# doorbell-controller.net
KiCad netlist of a schematic drawn in EAGLE
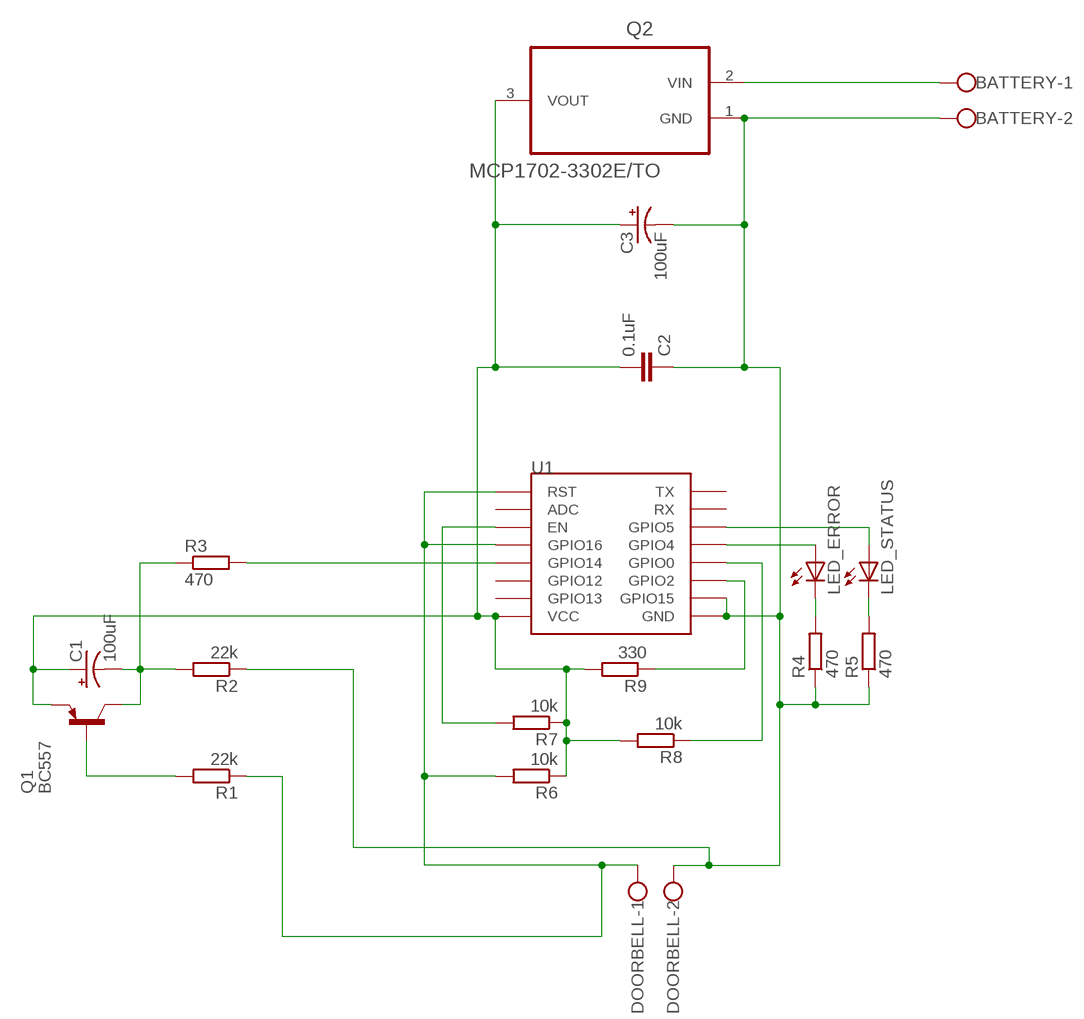
[diagram p0: schematic, sheet 1]

(export (version "E")
  (design (tool "Eeschema 10.0.6"))
  (components
    (comp (ref "BATTERY")
      (value "W237-102")
      (footprint "eagle-import:W237-102")
      (fields (field (name "MPN") "237-102"))
      (libsource (lib "eagle-import") (part "W237-102"))
    )
    (comp (ref "C1")
      (value "100uF")
      (footprint "eagle-import:E2,5-6E")
      (libsource (lib "eagle-import") (part "CPOL-USE2,5-6E"))
    )
    (comp (ref "C2")
      (value "0.1uF")
      (footprint "eagle-import:C025-025X050")
      (libsource (lib "eagle-import") (part "C-EU025-025X050"))
    )
    (comp (ref "C3")
      (value "100uF")
      (footprint "eagle-import:E2,5-6E")
      (libsource (lib "eagle-import") (part "CPOL-USE2,5-6E"))
    )
    (comp (ref "DOORBELL")
      (value "W237-102")
      (footprint "eagle-import:W237-102")
      (fields (field (name "MPN") "237-102"))
      (libsource (lib "eagle-import") (part "W237-102"))
    )
    (comp (ref "LED_ERROR")
      (value "LED5MM")
      (footprint "eagle-import:LED5MM")
      (libsource (lib "eagle-import") (part "LED5MM"))
    )
    (comp (ref "LED_STATUS")
      (value "LED5MM")
      (footprint "eagle-import:LED5MM")
      (libsource (lib "eagle-import") (part "LED5MM"))
    )
    (comp (ref "Q1")
      (value "BC557")
      (footprint "eagle-import:TO92")
      (libsource (lib "eagle-import") (part "BC557"))
    )
    (comp (ref "Q2")
      (value "MCP1702-3302E/TO")
      (footprint "eagle-import:TO127P254X533-3")
      (libsource (lib "eagle-import") (part "MCP1702-3302E/TO"))
    )
    (comp (ref "R1")
      (value "22k")
      (footprint "eagle-import:0204_7")
      (libsource (lib "eagle-import") (part "R-EU_0204/7"))
    )
    (comp (ref "R2")
      (value "22k")
      (footprint "eagle-import:0204_7")
      (libsource (lib "eagle-import") (part "R-EU_0204/7"))
    )
    (comp (ref "R3")
      (value "470")
      (footprint "eagle-import:0204_7")
      (libsource (lib "eagle-import") (part "R-EU_0204/7"))
    )
    (comp (ref "R4")
      (value "470")
      (footprint "eagle-import:0204_7")
      (libsource (lib "eagle-import") (part "R-EU_0204/7"))
    )
    (comp (ref "R5")
      (value "470")
      (footprint "eagle-import:0204_7")
      (libsource (lib "eagle-import") (part "R-EU_0204/7"))
    )
    (comp (ref "R6")
      (value "10k")
      (footprint "eagle-import:0204_7")
      (libsource (lib "eagle-import") (part "R-EU_0204/7"))
    )
    (comp (ref "R7")
      (value "10k")
      (footprint "eagle-import:0204_7")
      (libsource (lib "eagle-import") (part "R-EU_0204/7"))
    )
    (comp (ref "R8")
      (value "10k")
      (footprint "eagle-import:0204_7")
      (libsource (lib "eagle-import") (part "R-EU_0204/7"))
    )
    (comp (ref "R9")
      (value "330")
      (footprint "eagle-import:0204_7")
      (libsource (lib "eagle-import") (part "R-EU_0204/7"))
    )
    (comp (ref "U1")
      (value "ESP12-TR")
      (footprint "eagle-import:ESP12-TR")
      (libsource (lib "eagle-import") (part "ESP12-TR"))
    )
  )
  (nets
    (net (code "1") (name "Net-(BATTERYA-KL)") (class "Default")
      (node (ref "BATTERY") (pin "1") (pinfunction "KL_1") (pintype "passive"))
      (node (ref "Q2") (pin "2") (pinfunction "VIN_2") (pintype "input"))
    )
    (net (code "2") (name "Net-(BATTERYB-KL)") (class "Default")
      (node (ref "BATTERY") (pin "2") (pinfunction "KL_2") (pintype "passive"))
      (node (ref "C2") (pin "1") (pinfunction "1_1") (pintype "passive"))
      (node (ref "C3") (pin "-") (pinfunction "-_-") (pintype "passive"))
      (node (ref "DOORBELL") (pin "2") (pinfunction "KL_2") (pintype "passive"))
      (node (ref "Q2") (pin "1") (pinfunction "GND_1") (pintype "passive"))
      (node (ref "R2") (pin "1") (pinfunction "1_1") (pintype "passive"))
      (node (ref "R4") (pin "1") (pinfunction "1_1") (pintype "passive"))
      (node (ref "R5") (pin "1") (pinfunction "1_1") (pintype "passive"))
      (node (ref "U1") (pin "GND") (pinfunction "GND_GND") (pintype "bidirectional"))
      (node (ref "U1") (pin "GPIO15") (pinfunction "GPIO15_GPIO15") (pintype "bidirectional"))
    )
    (net (code "3") (name "Net-(DOORBELLA-KL)") (class "Default")
      (node (ref "DOORBELL") (pin "1") (pinfunction "KL_1") (pintype "passive"))
      (node (ref "R1") (pin "1") (pinfunction "1_1") (pintype "passive"))
      (node (ref "R6") (pin "2") (pinfunction "2_2") (pintype "passive"))
      (node (ref "U1") (pin "GPIO16") (pinfunction "GPIO16_GPIO16") (pintype "bidirectional"))
      (node (ref "U1") (pin "RST") (pinfunction "RST_RST") (pintype "bidirectional"))
    )
    (net (code "4") (name "Net-(LED_ERROR-C)") (class "Default")
      (node (ref "LED_ERROR") (pin "K") (pinfunction "C_K") (pintype "passive"))
      (node (ref "R4") (pin "2") (pinfunction "2_2") (pintype "passive"))
    )
    (net (code "5") (name "Net-(LED_ERROR-PadA)") (class "Default")
      (node (ref "LED_ERROR") (pin "A") (pinfunction "A_A") (pintype "passive"))
      (node (ref "U1") (pin "GPIO4") (pinfunction "GPIO4_GPIO4") (pintype "bidirectional"))
    )
    (net (code "6") (name "Net-(LED_STATUS-C)") (class "Default")
      (node (ref "LED_STATUS") (pin "K") (pinfunction "C_K") (pintype "passive"))
      (node (ref "R5") (pin "2") (pinfunction "2_2") (pintype "passive"))
    )
    (net (code "7") (name "Net-(LED_STATUS-PadA)") (class "Default")
      (node (ref "LED_STATUS") (pin "A") (pinfunction "A_A") (pintype "passive"))
      (node (ref "U1") (pin "GPIO5") (pinfunction "GPIO5_GPIO5") (pintype "bidirectional"))
    )
    (net (code "8") (name "Net-(Q1-B)") (class "Default")
      (node (ref "Q1") (pin "2") (pinfunction "B_2") (pintype "passive"))
      (node (ref "R1") (pin "2") (pinfunction "2_2") (pintype "passive"))
    )
    (net (code "9") (name "Net-(Q1-C)") (class "Default")
      (node (ref "C1") (pin "-") (pinfunction "-_-") (pintype "passive"))
      (node (ref "Q1") (pin "3") (pinfunction "C_3") (pintype "passive"))
      (node (ref "R2") (pin "2") (pinfunction "2_2") (pintype "passive"))
      (node (ref "R3") (pin "1") (pinfunction "1_1") (pintype "passive"))
    )
    (net (code "10") (name "Net-(Q1-E)") (class "Default")
      (node (ref "C1") (pin "+") (pinfunction "+_+") (pintype "passive"))
      (node (ref "C2") (pin "2") (pinfunction "2_2") (pintype "passive"))
      (node (ref "C3") (pin "+") (pinfunction "+_+") (pintype "passive"))
      (node (ref "Q1") (pin "1") (pinfunction "E_1") (pintype "passive"))
      (node (ref "Q2") (pin "3") (pinfunction "VOUT_3") (pintype "output"))
      (node (ref "R6") (pin "1") (pinfunction "1_1") (pintype "passive"))
      (node (ref "R7") (pin "1") (pinfunction "1_1") (pintype "passive"))
      (node (ref "R8") (pin "2") (pinfunction "2_2") (pintype "passive"))
      (node (ref "R9") (pin "2") (pinfunction "2_2") (pintype "passive"))
      (node (ref "U1") (pin "VCC") (pinfunction "VCC_VCC") (pintype "bidirectional"))
    )
    (net (code "11") (name "Net-(R3-Pad2)") (class "Default")
      (node (ref "R3") (pin "2") (pinfunction "2_2") (pintype "passive"))
      (node (ref "U1") (pin "GPIO14") (pinfunction "GPIO14_GPIO14") (pintype "bidirectional"))
    )
    (net (code "12") (name "Net-(R7-Pad2)") (class "Default")
      (node (ref "R7") (pin "2") (pinfunction "2_2") (pintype "passive"))
      (node (ref "U1") (pin "EN") (pinfunction "EN_EN") (pintype "bidirectional"))
    )
    (net (code "13") (name "Net-(R8-Pad1)") (class "Default")
      (node (ref "R8") (pin "1") (pinfunction "1_1") (pintype "passive"))
      (node (ref "U1") (pin "GPIO0") (pinfunction "GPIO0_GPIO0") (pintype "bidirectional"))
    )
    (net (code "14") (name "Net-(R9-Pad1)") (class "Default")
      (node (ref "R9") (pin "1") (pinfunction "1_1") (pintype "passive"))
      (node (ref "U1") (pin "GPIO2") (pinfunction "GPIO2_GPIO2") (pintype "bidirectional"))
    )
    (net (code "15") (name "unconnected-(U1-PadADC)") (class "Default")
      (node (ref "U1") (pin "ADC") (pinfunction "ADC_ADC") (pintype "bidirectional"))
    )
    (net (code "16") (name "unconnected-(U1-PadGPIO12)") (class "Default")
      (node (ref "U1") (pin "GPIO12") (pinfunction "GPIO12_GPIO12") (pintype "bidirectional"))
    )
    (net (code "17") (name "unconnected-(U1-PadGPIO13)") (class "Default")
      (node (ref "U1") (pin "GPIO13") (pinfunction "GPIO13_GPIO13") (pintype "bidirectional"))
    )
    (net (code "18") (name "unconnected-(U1-PadRX)") (class "Default")
      (node (ref "U1") (pin "RX") (pinfunction "RX_RX") (pintype "bidirectional"))
    )
    (net (code "19") (name "unconnected-(U1-PadTX)") (class "Default")
      (node (ref "U1") (pin "TX") (pinfunction "TX_TX") (pintype "bidirectional"))
    )
  )
)
